# MPU-Control.net
KiCad netlist of a schematic drawn in Altium Designer
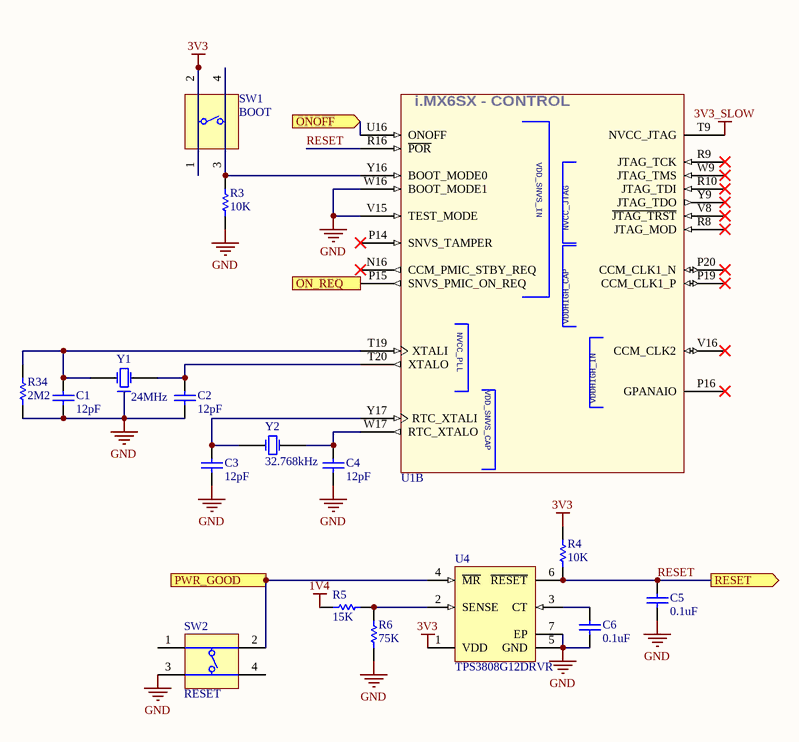
[diagram p0: MPU-Control.SchDoc]

(export (version "E")
  (design (tool "Eeschema 10.0.6"))
  (components
    (comp (ref "C1")
      (value "12pF")
      (footprint "C0402[1005X55]")
      (description "12pF 50V 5% 0402 (1005 Metric)")
      (fields (field (name "PARTNUMBER") "GRM1555C1H120JA01D") (field (name "MANUFACTURER") "Murata"))
      (libsource (lib "Capacitors") (part "CAP_12pF_50V_0402_5%"))
    )
    (comp (ref "C2")
      (value "12pF")
      (footprint "C0402[1005X55]")
      (description "12pF 50V 5% 0402 (1005 Metric)")
      (fields (field (name "PARTNUMBER") "GRM1555C1H120JA01D") (field (name "MANUFACTURER") "Murata"))
      (libsource (lib "Capacitors") (part "CAP_12pF_50V_0402_5%"))
    )
    (comp (ref "C3")
      (value "12pF")
      (footprint "C0402[1005X55]")
      (description "12pF 50V 5% 0402 (1005 Metric)")
      (fields (field (name "PARTNUMBER") "GRM1555C1H120JA01D") (field (name "MANUFACTURER") "Murata"))
      (libsource (lib "Capacitors") (part "CAP_12pF_50V_0402_5%"))
    )
    (comp (ref "C4")
      (value "12pF")
      (footprint "C0402[1005X55]")
      (description "12pF 50V 5% 0402 (1005 Metric)")
      (fields (field (name "PARTNUMBER") "GRM1555C1H120JA01D") (field (name "MANUFACTURER") "Murata"))
      (libsource (lib "Capacitors") (part "CAP_12pF_50V_0402_5%"))
    )
    (comp (ref "C5")
      (value "0.1uF")
      (footprint "C0402[1005X55]")
      (description "0.1uF 6.3V 10% 0402 (1005 Metric)")
      (fields (field (name "PARTNUMBER") "GRM155R70J104KA01D") (field (name "MANUFACTURER") "Murata"))
      (libsource (lib "Capacitors") (part "CAP_0.1uF_6.3V_0402_10%"))
    )
    (comp (ref "C6")
      (value "0.1uF")
      (footprint "C0402[1005X55]")
      (description "0.1uF 100V 10% 0402 (1005 Metric)")
      (fields (field (name "PARTNUMBER") "GRM155R62A104KE14D") (field (name "MANUFACTURER") "Murata"))
      (libsource (lib "Capacitors") (part "CAP_0.1uF_100V_0402_10%"))
    )
    (comp (ref "R3")
      (value "10K")
      (footprint "R0402[1005]")
      (description "10K 0.063W 1% 0402 (1005 Metric)")
      (fields (field (name "MANUFACTURER") "KOA Speer") (field (name "PARTNUMBER") "RK73H1ETTP1002F"))
      (libsource (lib "Resistors") (part "RES_10K_0402_1%"))
    )
    (comp (ref "R4")
      (value "10K")
      (footprint "R0402[1005]")
      (description "10K 0.063W 1% 0402 (1005 Metric)")
      (fields (field (name "MANUFACTURER") "KOA Speer") (field (name "PARTNUMBER") "RK73H1ETTP1002F"))
      (libsource (lib "Resistors") (part "RES_10K_0402_1%"))
    )
    (comp (ref "R5")
      (value "15K")
      (footprint "R0402[1005]")
      (description "15K 0.063W 1% 0402 (1005 Metric)")
      (fields (field (name "MANUFACTURER") "KOA Speer") (field (name "PARTNUMBER") "RK73H1ETTP1502F"))
      (libsource (lib "Resistors") (part "RES_15K_0402_1%"))
    )
    (comp (ref "R6")
      (value "75K")
      (footprint "R0402[1005]")
      (description "75K 0.063W 1% 0402 (1005 Metric)")
      (fields (field (name "MANUFACTURER") "KOA Speer") (field (name "PARTNUMBER") "RK73H1ETTP7502F"))
      (libsource (lib "Resistors") (part "RES_75K_0402_1%"))
    )
    (comp (ref "R34")
      (value "2M2")
      (footprint "R0402[1005]")
      (description "2M2 0.063W 1% 0402 (1005 Metric)")
      (fields (field (name "MANUFACTURER") "KOA Speer") (field (name "PARTNUMBER") "RK73H1ETTP2204F"))
      (libsource (lib "Resistors") (part "RES_2M2_0402_1%"))
    )
    (comp (ref "SW1")
      (value "BOOT")
      (footprint "SWITCH")
      (description "Switch, SPNO Push Button SMD")
      (fields
        (field (name "MANUFACTURER") "C&K Components")
        (field (name "PARTNUMBER") "PTS810 SJM 250 SMTR LFS")
      )
      (libsource (lib "") (part "DIPT-DTSM-6_1"))
    )
    (comp (ref "SW2")
      (value "RESET")
      (footprint "SWITCH")
      (description "Switch, SPNO Push Button SMD")
      (fields
        (field (name "MANUFACTURER") "C&K Components")
        (field (name "PARTNUMBER") "PTS810 SJM 250 SMTR LFS")
      )
      (libsource (lib "Components") (part "DIPT-DTSM-6"))
    )
    (comp (ref "U1")
      (value "MCIMX6X3EVO10AB")
      (footprint "BGA-400")
      (description "IC MPU I.MX6SX 1GHZ 400MAPBGA")
      (fields (field (name "MANUFACTURER") "NXP"))
      (libsource (lib "ICs") (part "MCIMX6X3EVO10AB"))
    )
    (comp (ref "U4")
      (value "TPS3808G12DRVR")
      (footprint "WSON-6")
      (fields (field (name "MANUFACTURER") "Texas Instruments"))
      (libsource (lib "ICs") (part "TPS3808G12DRVR"))
    )
    (comp (ref "Y1")
      (value "24MHz")
      (footprint "CRYSTAL_2.0x1.6")
      (fields (field (name "PARTNUMBER") "FA-128 24.0000MF10Z-W3") (field (name "MANUFACTURER") "EPSON"))
      (libsource (lib "Components") (part "FA-128 24.0000MF10Z-W3"))
    )
    (comp (ref "Y2")
      (value "32.768kHz")
      (footprint "CRYSTAL_2.0x1.2")
      (fields (field (name "PARTNUMBER") "ABS06-32.768KHZ-9-1-T") (field (name "MANUFACTURER") "Abracon"))
      (libsource (lib "Components") (part "ABS06-32.768KHZ-9-1-T"))
    )
  )
  (nets
    (net (code "1") (name "/ONOFF") (class "Default")
      (node (ref "U1") (pin "U16") (pinfunction "ONOFF_U16") (pintype "input"))
    )
    (net (code "2") (name "/ON_REQ") (class "Default")
      (node (ref "U1") (pin "P15") (pinfunction "SNVS_PMIC_ON_REQ_P15") (pintype "output"))
    )
    (net (code "3") (name "/PWR_GOOD") (class "Default")
      (node (ref "SW2") (pin "2") (pinfunction "T2_2") (pintype "passive"))
      (node (ref "U4") (pin "4") (pinfunction "~{MR}_4") (pintype "input"))
    )
    (net (code "4") (name "/RESET") (class "Default")
      (node (ref "C5") (pin "2") (pinfunction "2_2") (pintype "passive"))
      (node (ref "R4") (pin "1") (pinfunction "1_1") (pintype "passive"))
      (node (ref "U1") (pin "R16") (pinfunction "~{POR}_R16") (pintype "input"))
      (node (ref "U4") (pin "6") (pinfunction "~{RESET}_6") (pintype "tri_state"))
    )
    (net (code "5") (name "1V4") (class "Default")
      (node (ref "R5") (pin "2") (pinfunction "2_2") (pintype "passive"))
    )
    (net (code "6") (name "3V3") (class "Default")
      (node (ref "R4") (pin "2") (pinfunction "2_2") (pintype "passive"))
      (node (ref "SW1") (pin "1") (pinfunction "T1_1") (pintype "passive"))
      (node (ref "SW1") (pin "2") (pinfunction "T2_2") (pintype "passive"))
      (node (ref "U4") (pin "1") (pinfunction "VDD_1") (pintype "power_in"))
    )
    (net (code "7") (name "3V3_SLOW") (class "Default")
      (node (ref "U1") (pin "T9") (pinfunction "NVCC_JTAG_T9") (pintype "power_in"))
    )
    (net (code "8") (name "GND") (class "Default")
      (node (ref "C1") (pin "1") (pinfunction "1_1") (pintype "passive"))
      (node (ref "C2") (pin "1") (pinfunction "1_1") (pintype "passive"))
      (node (ref "C3") (pin "1") (pinfunction "1_1") (pintype "passive"))
      (node (ref "C4") (pin "1") (pinfunction "1_1") (pintype "passive"))
      (node (ref "C5") (pin "1") (pinfunction "1_1") (pintype "passive"))
      (node (ref "C6") (pin "1") (pinfunction "1_1") (pintype "passive"))
      (node (ref "R3") (pin "1") (pinfunction "1_1") (pintype "passive"))
      (node (ref "R34") (pin "1") (pinfunction "1_1") (pintype "passive"))
      (node (ref "R6") (pin "1") (pinfunction "1_1") (pintype "passive"))
      (node (ref "SW2") (pin "3") (pinfunction "T3_3") (pintype "passive"))
      (node (ref "U1") (pin "V15") (pinfunction "TEST_MODE_V15") (pintype "input"))
      (node (ref "U1") (pin "W16") (pinfunction "BOOT_MODE1_W16") (pintype "input"))
      (node (ref "U4") (pin "5") (pinfunction "GND_5") (pintype "power_in"))
      (node (ref "U4") (pin "7") (pinfunction "EP_7") (pintype "power_in"))
      (node (ref "Y1") (pin "2") (pinfunction "2_2") (pintype "passive"))
    )
    (net (code "9") (name "Net-(U1B-BOOT_MODE0)") (class "Default")
      (node (ref "R3") (pin "2") (pinfunction "2_2") (pintype "passive"))
      (node (ref "SW1") (pin "3") (pinfunction "T3_3") (pintype "passive"))
      (node (ref "SW1") (pin "4") (pinfunction "T3_4") (pintype "passive"))
      (node (ref "U1") (pin "Y16") (pinfunction "BOOT_MODE0_Y16") (pintype "input"))
    )
    (net (code "10") (name "Net-(U1B-RTC_XTALI)") (class "Default")
      (node (ref "C3") (pin "2") (pinfunction "2_2") (pintype "passive"))
      (node (ref "U1") (pin "Y17") (pinfunction "RTC_XTALI_Y17") (pintype "input"))
      (node (ref "Y2") (pin "1") (pinfunction "X1_1") (pintype "passive"))
    )
    (net (code "11") (name "Net-(U1B-RTC_XTALO)") (class "Default")
      (node (ref "C4") (pin "2") (pinfunction "2_2") (pintype "passive"))
      (node (ref "U1") (pin "W17") (pinfunction "RTC_XTALO_W17") (pintype "output"))
      (node (ref "Y2") (pin "2") (pinfunction "X2_2") (pintype "passive"))
    )
    (net (code "12") (name "Net-(U1B-XTALI)") (class "Default")
      (node (ref "C1") (pin "2") (pinfunction "2_2") (pintype "passive"))
      (node (ref "R34") (pin "2") (pinfunction "2_2") (pintype "passive"))
      (node (ref "U1") (pin "T19") (pinfunction "XTALI_T19") (pintype "input"))
      (node (ref "Y1") (pin "1") (pinfunction "X1_1") (pintype "passive"))
    )
    (net (code "13") (name "Net-(U1B-XTALO)") (class "Default")
      (node (ref "C2") (pin "2") (pinfunction "2_2") (pintype "passive"))
      (node (ref "U1") (pin "T20") (pinfunction "XTALO_T20") (pintype "output"))
      (node (ref "Y1") (pin "3") (pinfunction "X2_3") (pintype "passive"))
    )
    (net (code "14") (name "Net-(U4-CT)") (class "Default")
      (node (ref "C6") (pin "2") (pinfunction "2_2") (pintype "passive"))
      (node (ref "U4") (pin "3") (pinfunction "CT_3") (pintype "input"))
    )
    (net (code "15") (name "Net-(U4-SENSE)") (class "Default")
      (node (ref "R5") (pin "1") (pinfunction "1_1") (pintype "passive"))
      (node (ref "R6") (pin "2") (pinfunction "2_2") (pintype "passive"))
      (node (ref "U4") (pin "2") (pinfunction "SENSE_2") (pintype "input"))
    )
    (net (code "16") (name "unconnected-(SW2-T1-Pad1)") (class "Default")
      (node (ref "SW2") (pin "1") (pinfunction "T1_1") (pintype "passive"))
    )
    (net (code "17") (name "unconnected-(SW2-T3-Pad4)") (class "Default")
      (node (ref "SW2") (pin "4") (pinfunction "T3_4") (pintype "passive"))
    )
    (net (code "18") (name "unconnected-(U1B-CCM_CLK1_N-PadP20)") (class "Default")
      (node (ref "U1") (pin "P20") (pinfunction "CCM_CLK1_N_P20") (pintype "bidirectional+no_connect"))
    )
    (net (code "19") (name "unconnected-(U1B-CCM_CLK1_P-PadP19)") (class "Default")
      (node (ref "U1") (pin "P19") (pinfunction "CCM_CLK1_P_P19") (pintype "bidirectional+no_connect"))
    )
    (net (code "20") (name "unconnected-(U1B-CCM_CLK2-PadV16)") (class "Default")
      (node (ref "U1") (pin "V16") (pinfunction "CCM_CLK2_V16") (pintype "bidirectional+no_connect"))
    )
    (net (code "21") (name "unconnected-(U1B-CCM_PMIC_STBY_REQ-PadN16)") (class "Default")
      (node (ref "U1") (pin "N16") (pinfunction "CCM_PMIC_STBY_REQ_N16") (pintype "output+no_connect"))
    )
    (net (code "22") (name "unconnected-(U1B-GPANAIO-PadP16)") (class "Default")
      (node (ref "U1") (pin "P16") (pinfunction "GPANAIO_P16") (pintype "power_in+no_connect"))
    )
    (net (code "23") (name "unconnected-(U1B-JTAG_MOD-PadR8)") (class "Default")
      (node (ref "U1") (pin "R8") (pinfunction "JTAG_MOD_R8") (pintype "input+no_connect"))
    )
    (net (code "24") (name "unconnected-(U1B-JTAG_TCK-PadR9)") (class "Default")
      (node (ref "U1") (pin "R9") (pinfunction "JTAG_TCK_R9") (pintype "input+no_connect"))
    )
    (net (code "25") (name "unconnected-(U1B-JTAG_TDI-PadR10)") (class "Default")
      (node (ref "U1") (pin "R10") (pinfunction "JTAG_TDI_R10") (pintype "input+no_connect"))
    )
    (net (code "26") (name "unconnected-(U1B-JTAG_TDO-PadY9)") (class "Default")
      (node (ref "U1") (pin "Y9") (pinfunction "JTAG_TDO_Y9") (pintype "output+no_connect"))
    )
    (net (code "27") (name "unconnected-(U1B-JTAG_TMS-PadW9)") (class "Default")
      (node (ref "U1") (pin "W9") (pinfunction "JTAG_TMS_W9") (pintype "input+no_connect"))
    )
    (net (code "28") (name "unconnected-(U1B-SNVS_TAMPER-PadP14)") (class "Default")
      (node (ref "U1") (pin "P14") (pinfunction "SNVS_TAMPER_P14") (pintype "input+no_connect"))
    )
    (net (code "29") (name "unconnected-(U1B-~{JTAG_TRST}-PadV8)") (class "Default")
      (node (ref "U1") (pin "V8") (pinfunction "~{JTAG_TRST}_V8") (pintype "input+no_connect"))
    )
  )
)
